# Sheet1.net
KiCad netlist of a schematic drawn in Altium Designer
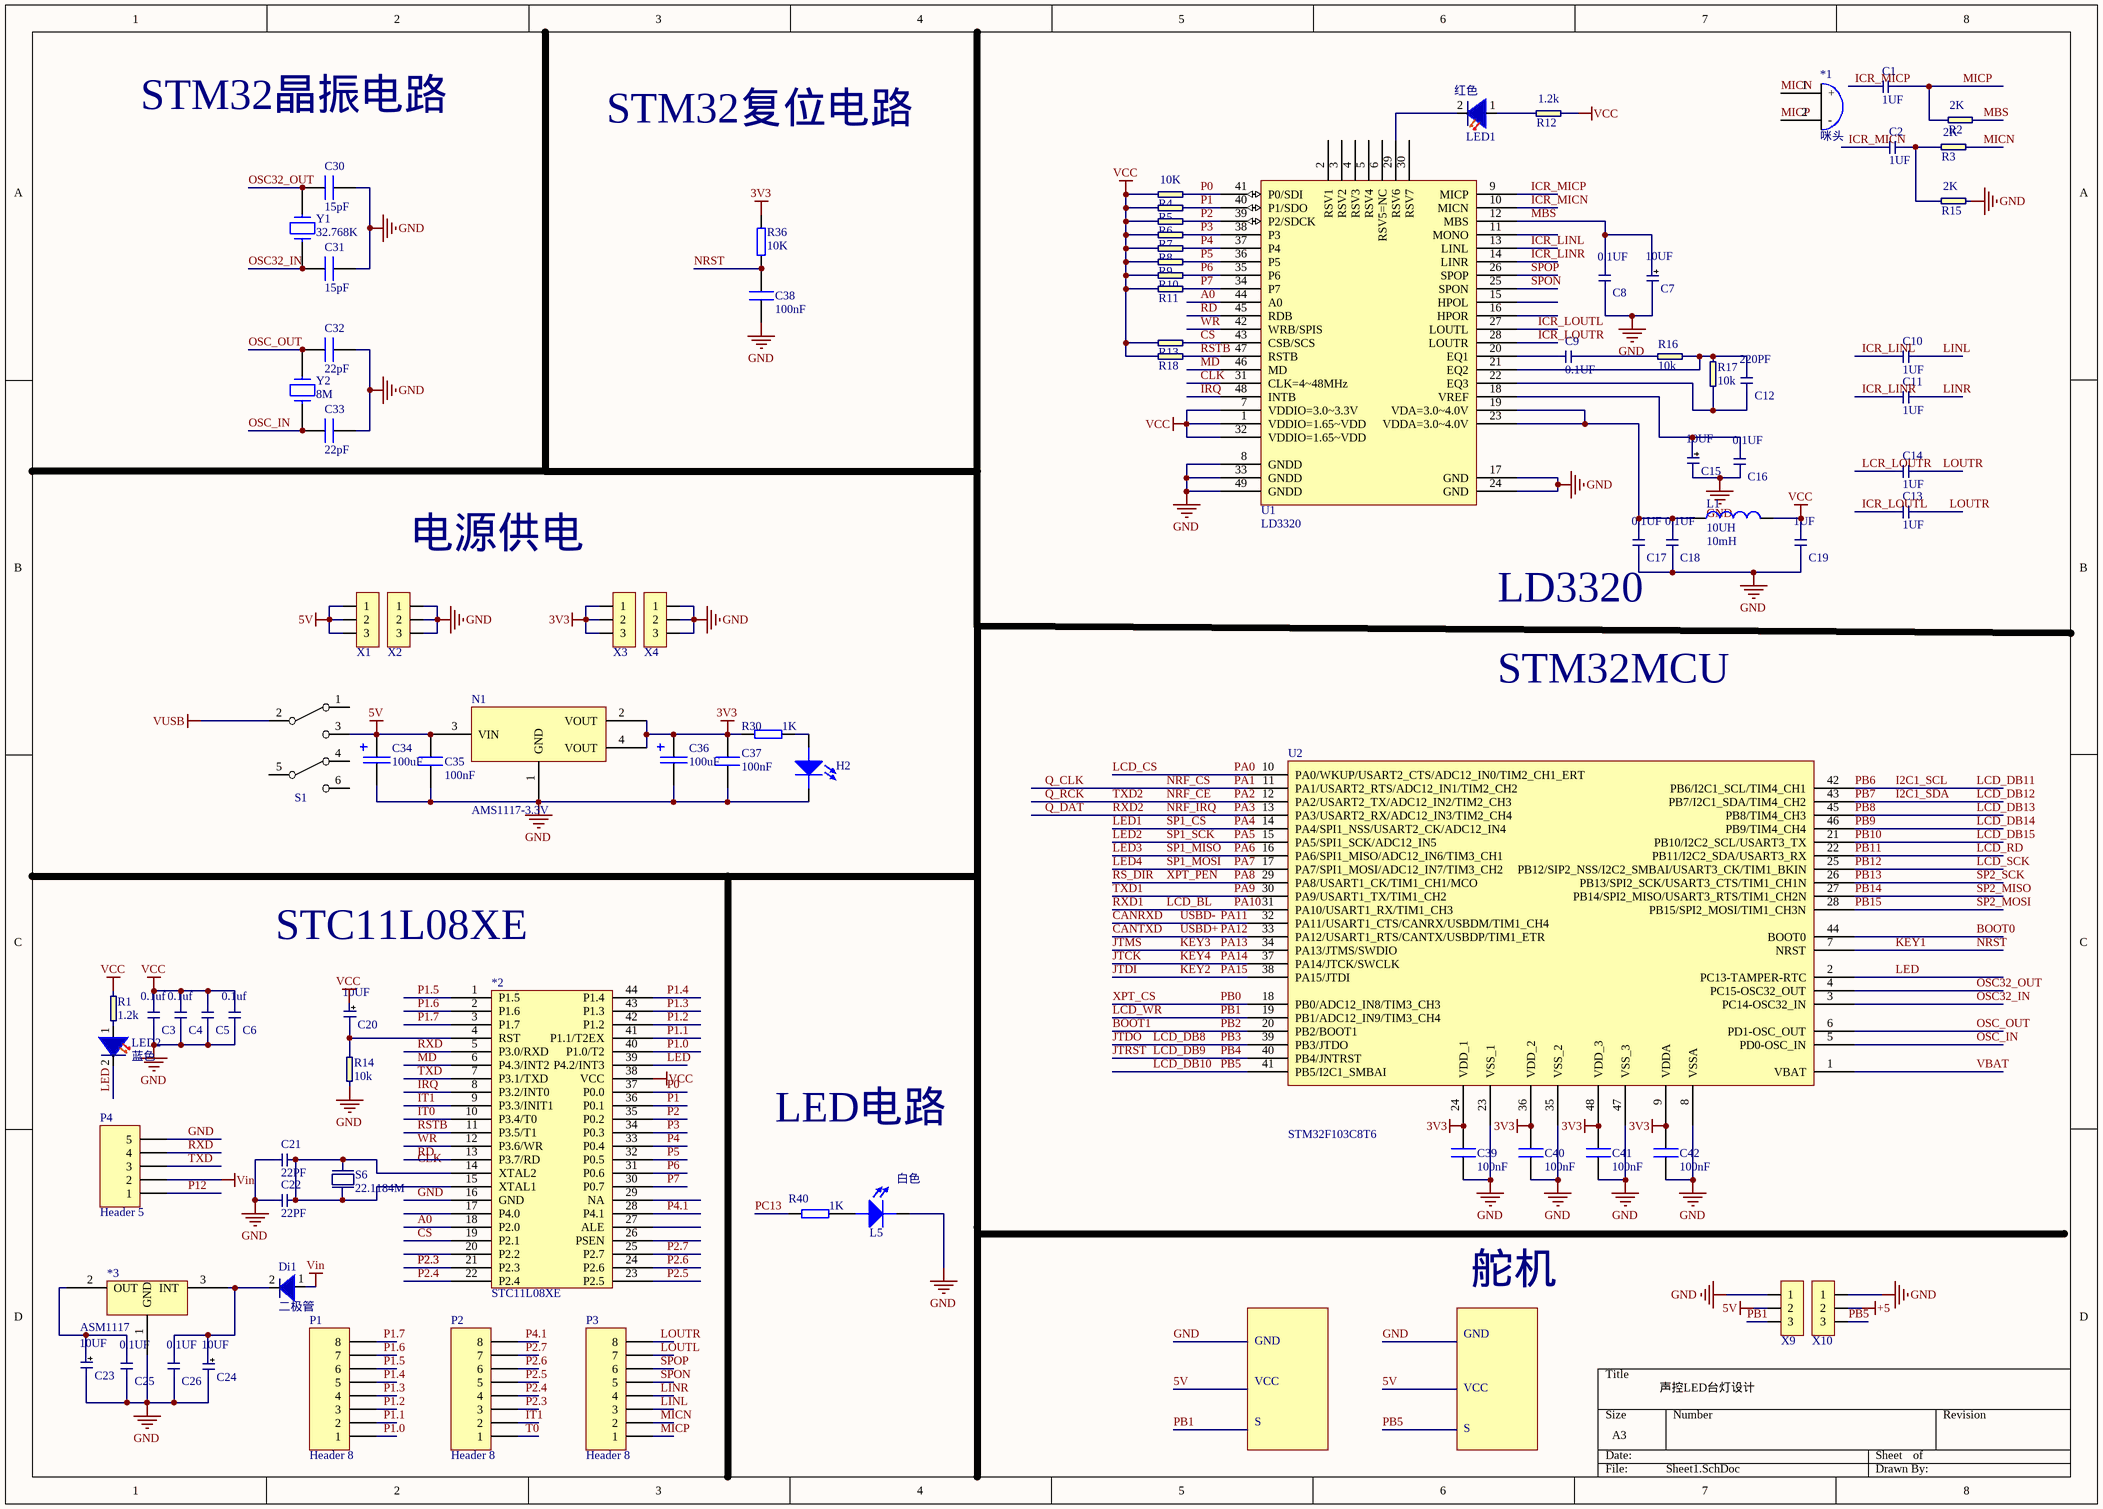
[diagram p0: Sheet1.SchDoc]

(export (version "E")
  (design (tool "Eeschema 10.0.6"))
  (components
    (comp (ref "*1") (value "咪头") (footprint "CAPPR5-5x5") (libsource (lib "LD3320原理图") (part "咪头")))
    (comp (ref "*2")
      (value "STC11L08XE")
      (footprint "LQFP44")
      (libsource (lib "LD3320原理图") (part "STC11L08XE"))
    )
    (comp (ref "*3") (value "ASM1117") (footprint "ASM1117") (libsource (lib "LD3320原理图") (part "ASM1117")))
    (comp (ref "C1") (value "1UF") (footprint "CT2mm") (libsource (lib "MYPCB") (part "瓷片电容")))
    (comp (ref "C2") (value "1UF") (footprint "CT2mm") (libsource (lib "MYPCB") (part "瓷片电容")))
    (comp (ref "C3") (value "0.1uf") (footprint "CT2mm") (libsource (lib "杨氏-元件库") (part "瓷片电容")))
    (comp (ref "C4") (value "0.1uf") (footprint "CT2mm") (libsource (lib "杨氏-元件库") (part "瓷片电容")))
    (comp (ref "C5") (value "0.1uf") (footprint "CT2mm") (libsource (lib "杨氏-元件库") (part "瓷片电容")))
    (comp (ref "C6") (value "0.1uf") (footprint "CT2mm") (libsource (lib "杨氏-元件库") (part "瓷片电容")))
    (comp (ref "C7") (value "10UF") (footprint "Rt2mm") (libsource (lib "MYPCB") (part "电解电容")))
    (comp (ref "C8") (value "0.1UF") (footprint "CT2mm") (libsource (lib "MYPCB") (part "瓷片电容")))
    (comp (ref "C9") (value "0.1UF") (footprint "CT2mm") (libsource (lib "MYPCB") (part "瓷片电容")))
    (comp (ref "C10") (value "1UF") (footprint "CT2mm") (libsource (lib "MYPCB") (part "瓷片电容")))
    (comp (ref "C11") (value "1UF") (footprint "CT2mm") (libsource (lib "MYPCB") (part "瓷片电容")))
    (comp (ref "C12") (value "220PF") (footprint "CT2mm") (libsource (lib "MYPCB") (part "瓷片电容")))
    (comp (ref "C13") (value "1UF") (footprint "CT2mm") (libsource (lib "MYPCB") (part "瓷片电容")))
    (comp (ref "C14") (value "1UF") (footprint "CT2mm") (libsource (lib "MYPCB") (part "瓷片电容")))
    (comp (ref "C15") (value "10UF") (footprint "Rt2mm") (libsource (lib "MYPCB") (part "电解电容")))
    (comp (ref "C16") (value "0.1UF") (footprint "CT2mm") (libsource (lib "MYPCB") (part "瓷片电容")))
    (comp (ref "C17") (value "0.1UF") (footprint "CT2mm") (libsource (lib "MYPCB") (part "瓷片电容")))
    (comp (ref "C18") (value "0.1UF") (footprint "CT2mm") (libsource (lib "MYPCB") (part "瓷片电容")))
    (comp (ref "C19") (value "1UF") (footprint "CT2mm") (libsource (lib "MYPCB") (part "瓷片电容")))
    (comp (ref "C20") (value "10UF") (footprint "Rt2mm") (libsource (lib "MYPCB") (part "电解电容")))
    (comp (ref "C21") (value "22PF") (footprint "CT2mm") (libsource (lib "MYPCB") (part "瓷片电容")))
    (comp (ref "C22") (value "22PF") (footprint "CT2mm") (libsource (lib "MYPCB") (part "瓷片电容")))
    (comp (ref "C23") (value "10UF") (footprint "Rt2mm") (libsource (lib "MYPCB") (part "电解电容")))
    (comp (ref "C24") (value "10UF") (footprint "Rt2mm") (libsource (lib "MYPCB") (part "电解电容")))
    (comp (ref "C25") (value "0.1UF") (footprint "CT2mm") (libsource (lib "MYPCB") (part "瓷片电容")))
    (comp (ref "C26") (value "0.1UF") (footprint "CT2mm") (libsource (lib "MYPCB") (part "瓷片电容")))
    (comp (ref "C30")
      (value "15pF")
      (footprint "C0805")
      (description "Capacitor")
      (libsource (lib "Liuzhx") (part "普通贴片电容"))
    )
    (comp (ref "C31")
      (value "15pF")
      (footprint "C0805")
      (description "Capacitor")
      (libsource (lib "Liuzhx") (part "普通贴片电容"))
    )
    (comp (ref "C32")
      (value "22pF")
      (footprint "C0805")
      (description "Capacitor")
      (libsource (lib "Liuzhx") (part "普通贴片电容"))
    )
    (comp (ref "C33")
      (value "22pF")
      (footprint "C0805")
      (description "Capacitor")
      (libsource (lib "Liuzhx") (part "普通贴片电容"))
    )
    (comp (ref "C34") (value "100uF") (footprint "CAP5*5_4") (libsource (lib "Liuzhx") (part "极性电容器")))
    (comp (ref "C35")
      (value "100nF")
      (footprint "C0805")
      (description "Capacitor")
      (libsource (lib "Liuzhx") (part "普通贴片电容"))
    )
    (comp (ref "C36") (value "100uF") (footprint "CAP5*5_4") (libsource (lib "Liuzhx") (part "极性电容器")))
    (comp (ref "C37")
      (value "100nF")
      (footprint "C0805")
      (description "Capacitor")
      (libsource (lib "Liuzhx") (part "普通贴片电容"))
    )
    (comp (ref "C38")
      (value "100nF")
      (footprint "C0805")
      (description "Capacitor")
      (libsource (lib "Liuzhx") (part "普通贴片电容"))
    )
    (comp (ref "C39")
      (value "100nF")
      (footprint "C0805")
      (description "Capacitor")
      (libsource (lib "Liuzhx") (part "普通贴片电容"))
    )
    (comp (ref "C40")
      (value "100nF")
      (footprint "C0805")
      (description "Capacitor")
      (libsource (lib "Liuzhx") (part "普通贴片电容"))
    )
    (comp (ref "C41")
      (value "100nF")
      (footprint "C0805")
      (description "Capacitor")
      (libsource (lib "Liuzhx") (part "普通贴片电容"))
    )
    (comp (ref "C42")
      (value "100nF")
      (footprint "C0805")
      (description "Capacitor")
      (libsource (lib "Liuzhx") (part "普通贴片电容"))
    )
    (comp (ref "Di1") (value "二极管") (footprint "DT4mm") (libsource (lib "MYPCB") (part "二极管")))
    (comp (ref "H2") (value "发光二极管") (footprint "LED1206") (libsource (lib "Liuzhx") (part "发光二极管")))
    (comp (ref "L1")
      (value "10UH")
      (footprint "INDC1005AL")
      (description "Inductor")
      (fields (field (name "ALTIUM_VALUE") "10mH") (field (name "PUBLISHER") "Altium Limited"))
      (libsource (lib "Miscellaneous Devices") (part "Inductor"))
    )
    (comp (ref "L5") (value "发光二极管") (footprint "LED1206") (libsource (lib "Liuzhx") (part "发光二极管")))
    (comp (ref "LED1") (value "红色") (footprint "LEDT") (libsource (lib "MYPCB") (part "LED")))
    (comp (ref "LED2") (value "蓝色") (footprint "LEDT") (libsource (lib "MYPCB") (part "LED")))
    (comp (ref "N1")
      (value "AMS1117-3.3V")
      (footprint "SOT223")
      (libsource (lib "Liuzhx") (part "AMS1117-3.3V"))
    )
    (comp (ref "P1")
      (value "Header 8")
      (footprint "HD8")
      (description "Header, 8-Pin")
      (fields (field (name "PUBLISHER") "Altium Limited"))
      (libsource (lib "MYPCB") (part "Header 8"))
    )
    (comp (ref "P2")
      (value "Header 8")
      (footprint "HD8")
      (description "Header, 8-Pin")
      (fields (field (name "PUBLISHER") "Altium Limited"))
      (libsource (lib "MYPCB") (part "Header 8"))
    )
    (comp (ref "P3")
      (value "Header 8")
      (footprint "HD8")
      (description "Header, 8-Pin")
      (fields (field (name "PUBLISHER") "Altium Limited"))
      (libsource (lib "MYPCB") (part "Header 8"))
    )
    (comp (ref "P4")
      (value "Header 5")
      (footprint "HD5")
      (description "Header, 5-Pin")
      (fields (field (name "PUBLISHER") "Altium Limited"))
      (libsource (lib "MYPCB") (part "Header 5"))
    )
    (comp (ref "R1") (value "1.2k") (footprint "Rt2mm") (libsource (lib "") (part "RES_2")))
    (comp (ref "R2") (value "2K") (footprint "Rt2mm") (libsource (lib "") (part "RES_1")))
    (comp (ref "R3") (value "2K") (footprint "Rt2mm") (libsource (lib "") (part "RES_1")))
    (comp (ref "R4") (value "10K") (footprint "Rt2mm") (libsource (lib "") (part "RES_1")))
    (comp (ref "R5") (value "RES") (footprint "Rt2mm") (libsource (lib "") (part "RES_1")))
    (comp (ref "R6") (value "RES") (footprint "Rt2mm") (libsource (lib "") (part "RES_1")))
    (comp (ref "R7") (value "RES") (footprint "Rt2mm") (libsource (lib "") (part "RES_1")))
    (comp (ref "R8") (value "RES") (footprint "Rt2mm") (libsource (lib "") (part "RES_1")))
    (comp (ref "R9") (value "RES") (footprint "Rt2mm") (libsource (lib "") (part "RES_1")))
    (comp (ref "R10") (value "RES") (footprint "Rt2mm") (libsource (lib "") (part "RES_1")))
    (comp (ref "R11") (value "RES") (footprint "Rt2mm") (libsource (lib "") (part "RES_1")))
    (comp (ref "R12") (value "1.2k") (footprint "Rt2mm") (libsource (lib "") (part "RES_1")))
    (comp (ref "R13") (value "RES") (footprint "Rt2mm") (libsource (lib "") (part "RES_1")))
    (comp (ref "R14") (value "10k") (footprint "Rt2mm") (libsource (lib "") (part "RES_2")))
    (comp (ref "R15") (value "2K") (footprint "Rt2mm") (libsource (lib "") (part "RES_1")))
    (comp (ref "R16") (value "10k") (footprint "Rt2mm") (libsource (lib "MYPCB") (part "RES")))
    (comp (ref "R17") (value "10k") (footprint "Rt2mm") (libsource (lib "") (part "RES_2")))
    (comp (ref "R18") (value "RES") (footprint "Rt2mm") (libsource (lib "") (part "RES_1")))
    (comp (ref "R30") (value "1K") (footprint "R0805") (libsource (lib "Liuzhx") (part "普通贴片电阻")))
    (comp (ref "R36") (value "10K") (footprint "R0805") (libsource (lib "Liuzhx") (part "普通贴片电阻")))
    (comp (ref "R40") (value "1K") (footprint "R0805") (libsource (lib "Liuzhx") (part "普通贴片电阻")))
    (comp (ref "S1") (value "SWITCH-6") (footprint "SW-AJ") (libsource (lib "Liuzhx") (part "SWITCH-6")))
    (comp (ref "S6") (value "22.1184M") (footprint "晶振") (libsource (lib "MYPCB") (part "Y1")))
    (comp (ref "U1")
      (value "LD3320")
      (footprint "QFN50P700X700X80-48N")
      (libsource (lib "LD3320原理图") (part "Component_1"))
    )
    (comp (ref "U2")
      (value "STM32F103C8T6")
      (footprint "LQFP48")
      (libsource (lib "STM32F103-V1.0") (part "STM32F103C8T6"))
    )
    (comp (ref "X1")
      (value "JX3")
      (footprint "SIP3")
      (description "Connector")
      (libsource (lib "") (part "JX3_1"))
    )
    (comp (ref "X2")
      (value "JX3")
      (footprint "SIP3")
      (description "Connector")
      (libsource (lib "Liuzhx") (part "JX3"))
    )
    (comp (ref "X3")
      (value "JX3")
      (footprint "SIP3")
      (description "Connector")
      (libsource (lib "") (part "JX3_1"))
    )
    (comp (ref "X4")
      (value "JX3")
      (footprint "SIP3")
      (description "Connector")
      (libsource (lib "Liuzhx") (part "JX3"))
    )
    (comp (ref "X9")
      (value "JX3")
      (footprint "SIP3")
      (description "Connector")
      (libsource (lib "") (part "JX3_1"))
    )
    (comp (ref "X10")
      (value "JX3")
      (footprint "SIP3")
      (description "Connector")
      (libsource (lib "Liuzhx") (part "JX3"))
    )
    (comp (ref "Y1")
      (value "32.768K")
      (footprint "FC135")
      (description "Crystal")
      (libsource (lib "Liuzhx") (part "CRYSTAL"))
    )
    (comp (ref "Y2")
      (value "8M")
      (footprint "JZ-AX")
      (description "Crystal")
      (libsource (lib "Liuzhx") (part "CRYSTAL"))
    )
  )
  (nets
    (net (code "1") (name "+5") (class "Default")
      (node (ref "X10") (pin "2") (pinfunction "2_2") (pintype "passive"))
    )
    (net (code "2") (name "/A0") (class "Default")
      (node (ref "*2") (pin "18") (pinfunction "P2.0_18") (pintype "passive"))
      (node (ref "U1") (pin "44") (pinfunction "A0_44") (pintype "passive"))
    )
    (net (code "3") (name "/BOOT0") (class "Default")
      (node (ref "U2") (pin "44") (pinfunction "BOOT0_44") (pintype "passive"))
    )
    (net (code "4") (name "/BOOT1") (class "Default")
      (node (ref "U2") (pin "20") (pinfunction "PB2/BOOT1_20") (pintype "passive"))
    )
    (net (code "5") (name "/CANRXD") (class "Default")
      (node (ref "U2") (pin "32") (pinfunction "PA11/USART1_CTS/CANRX/USBDM/TIM1_CH4_32") (pintype "passive"))
    )
    (net (code "6") (name "/CANTXD") (class "Default")
      (node (ref "U2") (pin "33") (pinfunction "PA12/USART1_RTS/CANTX/USBDP/TIM1_ETR_33") (pintype "passive"))
    )
    (net (code "7") (name "/CLK") (class "Default")
      (node (ref "U1") (pin "31") (pinfunction "CLK=4~48MHz_31") (pintype "passive"))
    )
    (net (code "8") (name "/CS") (class "Default")
      (node (ref "*2") (pin "19") (pinfunction "P2.1_19") (pintype "passive"))
      (node (ref "R13") (pin "2") (pinfunction "2_2") (pintype "passive"))
      (node (ref "U1") (pin "43") (pinfunction "CSB/SCS_43") (pintype "passive"))
    )
    (net (code "9") (name "/I2C1_SCL") (class "Default")
      (node (ref "U2") (pin "42") (pinfunction "PB6/I2C1_SCL/TIM4_CH1_42") (pintype "passive"))
    )
    (net (code "10") (name "/I2C1_SDA") (class "Default")
      (node (ref "U2") (pin "43") (pinfunction "PB7/I2C1_SDA/TIM4_CH2_43") (pintype "passive"))
    )
    (net (code "11") (name "/ICR_LINL") (class "Default")
      (node (ref "C10") (pin "2") (pinfunction "2_2") (pintype "passive"))
      (node (ref "U1") (pin "13") (pinfunction "LINL_13") (pintype "passive"))
    )
    (net (code "12") (name "/ICR_LINR") (class "Default")
      (node (ref "C11") (pin "2") (pinfunction "2_2") (pintype "passive"))
      (node (ref "U1") (pin "14") (pinfunction "LINR_14") (pintype "passive"))
    )
    (net (code "13") (name "/ICR_LOUTL") (class "Default")
      (node (ref "C13") (pin "2") (pinfunction "2_2") (pintype "passive"))
      (node (ref "U1") (pin "27") (pinfunction "LOUTL_27") (pintype "passive"))
    )
    (net (code "14") (name "/ICR_LOUTR") (class "Default")
      (node (ref "U1") (pin "28") (pinfunction "LOUTR_28") (pintype "passive"))
    )
    (net (code "15") (name "/ICR_MICN") (class "Default")
      (node (ref "C2") (pin "2") (pinfunction "2_2") (pintype "passive"))
      (node (ref "U1") (pin "10") (pinfunction "MICN_10") (pintype "passive"))
    )
    (net (code "16") (name "/ICR_MICP") (class "Default")
      (node (ref "C1") (pin "2") (pinfunction "2_2") (pintype "passive"))
      (node (ref "U1") (pin "9") (pinfunction "MICP_9") (pintype "passive"))
    )
    (net (code "17") (name "/IRQ") (class "Default")
      (node (ref "*2") (pin "8") (pinfunction "P3.2/INT0_8") (pintype "passive"))
      (node (ref "U1") (pin "48") (pinfunction "INTB_48") (pintype "passive"))
    )
    (net (code "18") (name "/IT0") (class "Default")
      (node (ref "*2") (pin "10") (pinfunction "P3.4/T0_10") (pintype "passive"))
    )
    (net (code "19") (name "/IT1") (class "Default")
      (node (ref "*2") (pin "9") (pinfunction "P3.3/INIT1_9") (pintype "passive"))
      (node (ref "P2") (pin "2") (pinfunction "2_2") (pintype "passive"))
    )
    (net (code "20") (name "/JTCK") (class "Default")
      (node (ref "U2") (pin "37") (pinfunction "PA14/JTCK/SWCLK_37") (pintype "passive"))
    )
    (net (code "21") (name "/JTDI") (class "Default")
      (node (ref "U2") (pin "38") (pinfunction "PA15/JTDI_38") (pintype "passive"))
    )
    (net (code "22") (name "/JTDO") (class "Default")
      (node (ref "U2") (pin "39") (pinfunction "PB3/JTDO_39") (pintype "passive"))
    )
    (net (code "23") (name "/JTMS") (class "Default")
      (node (ref "U2") (pin "34") (pinfunction "PA13/JTMS/SWDIO_34") (pintype "passive"))
    )
    (net (code "24") (name "/JTRST") (class "Default")
      (node (ref "U2") (pin "40") (pinfunction "PB4/JNTRST_40") (pintype "passive"))
    )
    (net (code "25") (name "/KEY1") (class "Default")
      (node (ref "C38") (pin "2") (pinfunction "2_2") (pintype "passive"))
      (node (ref "R36") (pin "1") (pinfunction "1_1") (pintype "passive"))
      (node (ref "U2") (pin "7") (pinfunction "NRST_7") (pintype "passive"))
    )
    (net (code "26") (name "/LCD_BL") (class "Default")
      (node (ref "U2") (pin "31") (pinfunction "PA10/USART1_RX/TIM1_CH3_31") (pintype "passive"))
    )
    (net (code "27") (name "/LCD_CS") (class "Default")
      (node (ref "U2") (pin "10") (pinfunction "PA0/WKUP/USART2_CTS/ADC12_IN0/TIM2_CH1_ERT_10") (pintype "passive"))
    )
    (net (code "28") (name "/LCD_DB10") (class "Default")
      (node (ref "U2") (pin "41") (pinfunction "PB5/I2C1_SMBAI_41") (pintype "passive"))
      (node (ref "X10") (pin "3") (pinfunction "3_3") (pintype "passive"))
    )
    (net (code "29") (name "/LCD_DB13") (class "Default")
      (node (ref "U2") (pin "45") (pinfunction "PB8/TIM4_CH3_45") (pintype "passive"))
    )
    (net (code "30") (name "/LCD_DB14") (class "Default")
      (node (ref "U2") (pin "46") (pinfunction "PB9/TIM4_CH4_46") (pintype "passive"))
    )
    (net (code "31") (name "/LCD_DB15") (class "Default")
      (node (ref "U2") (pin "21") (pinfunction "PB10/I2C2_SCL/USART3_TX_21") (pintype "passive"))
    )
    (net (code "32") (name "/LCD_RD") (class "Default")
      (node (ref "U2") (pin "22") (pinfunction "PB11/I2C2_SDA/USART3_RX_22") (pintype "passive"))
    )
    (net (code "33") (name "/LCD_SCK") (class "Default")
      (node (ref "U2") (pin "25") (pinfunction "PB12/SIP2_NSS/I2C2_SMBAI/USART3_CK/TIM1_BKIN_25") (pintype "passive"))
    )
    (net (code "34") (name "/LCD_WR") (class "Default")
      (node (ref "U2") (pin "19") (pinfunction "PB1/ADC12_IN9/TIM3_CH4_19") (pintype "passive"))
      (node (ref "X9") (pin "3") (pinfunction "3_3") (pintype "passive"))
    )
    (net (code "35") (name "/LCR_LOUTR") (class "Default")
      (node (ref "C14") (pin "2") (pinfunction "2_2") (pintype "passive"))
    )
    (net (code "36") (name "/LED") (class "Default")
      (node (ref "*2") (pin "39") (pinfunction "P4.2/INT3_39") (pintype "passive"))
      (node (ref "LED2") (pin "2") (pinfunction "2_2") (pintype "passive"))
      (node (ref "U2") (pin "2") (pinfunction "PC13-TAMPER-RTC_2") (pintype "passive"))
    )
    (net (code "37") (name "/LED1") (class "Default")
      (node (ref "U2") (pin "14") (pinfunction "PA4/SPI1_NSS/USART2_CK/ADC12_IN4_14") (pintype "passive"))
    )
    (net (code "38") (name "/LED2") (class "Default")
      (node (ref "U2") (pin "15") (pinfunction "PA5/SPI1_SCK/ADC12_IN5_15") (pintype "passive"))
    )
    (net (code "39") (name "/LED3") (class "Default")
      (node (ref "U2") (pin "16") (pinfunction "PA6/SPI1_MISO/ADC12_IN6/TIM3_CH1_16") (pintype "passive"))
    )
    (net (code "40") (name "/LED4") (class "Default")
      (node (ref "U2") (pin "17") (pinfunction "PA7/SPI1_MOSI/ADC12_IN7/TIM3_CH2_17") (pintype "passive"))
    )
    (net (code "41") (name "/LINL") (class "Default")
      (node (ref "C10") (pin "1") (pinfunction "1_1") (pintype "passive"))
      (node (ref "P3") (pin "3") (pinfunction "3_3") (pintype "passive"))
    )
    (net (code "42") (name "/LINR") (class "Default")
      (node (ref "C11") (pin "1") (pinfunction "1_1") (pintype "passive"))
      (node (ref "P3") (pin "4") (pinfunction "4_4") (pintype "passive"))
    )
    (net (code "43") (name "/LOUTL") (class "Default")
      (node (ref "P3") (pin "7") (pinfunction "7_7") (pintype "passive"))
    )
    (net (code "44") (name "/LOUTR") (class "Default")
      (node (ref "C13") (pin "1") (pinfunction "1_1") (pintype "passive"))
      (node (ref "C14") (pin "1") (pinfunction "1_1") (pintype "passive"))
      (node (ref "P3") (pin "8") (pinfunction "8_8") (pintype "passive"))
    )
    (net (code "45") (name "/MBS") (class "Default")
      (node (ref "C7") (pin "1") (pinfunction "1_1") (pintype "passive"))
      (node (ref "C8") (pin "2") (pinfunction "2_2") (pintype "passive"))
      (node (ref "R2") (pin "2") (pinfunction "2_2") (pintype "passive"))
      (node (ref "U1") (pin "12") (pinfunction "MBS_12") (pintype "passive"))
    )
    (net (code "46") (name "/MD") (class "Default")
      (node (ref "*2") (pin "6") (pinfunction "P4.3/INT2_6") (pintype "passive"))
      (node (ref "U1") (pin "46") (pinfunction "MD_46") (pintype "passive"))
    )
    (net (code "47") (name "/MICN") (class "Default")
      (node (ref "*1") (pin "1") (pinfunction "+_1") (pintype "passive"))
      (node (ref "P3") (pin "2") (pinfunction "2_2") (pintype "passive"))
      (node (ref "R3") (pin "2") (pinfunction "2_2") (pintype "passive"))
    )
    (net (code "48") (name "/MICP") (class "Default")
      (node (ref "*1") (pin "2") (pinfunction "-_2") (pintype "passive"))
      (node (ref "C1") (pin "1") (pinfunction "1_1") (pintype "passive"))
      (node (ref "P3") (pin "1") (pinfunction "1_1") (pintype "passive"))
      (node (ref "R2") (pin "1") (pinfunction "1_1") (pintype "passive"))
    )
    (net (code "49") (name "/NRF_CE") (class "Default")
      (node (ref "U2") (pin "12") (pinfunction "PA2/USART2_TX/ADC12_IN2/TIM2_CH3_12") (pintype "passive"))
    )
    (net (code "50") (name "/NRF_CS") (class "Default")
      (node (ref "U2") (pin "11") (pinfunction "PA1/USART2_RTS/ADC12_IN1/TIM2_CH2_11") (pintype "passive"))
    )
    (net (code "51") (name "/NRF_IRQ") (class "Default")
      (node (ref "U2") (pin "13") (pinfunction "PA3/USART2_RX/ADC12_IN3/TIM2_CH4_13") (pintype "passive"))
    )
    (net (code "52") (name "/OSC32_IN") (class "Default")
      (node (ref "C31") (pin "1") (pinfunction "1_1") (pintype "passive"))
      (node (ref "U2") (pin "3") (pinfunction "PC14-OSC32_IN_3") (pintype "passive"))
      (node (ref "Y1") (pin "1") (pinfunction "1_1") (pintype "passive"))
    )
    (net (code "53") (name "/OSC32_OUT") (class "Default")
      (node (ref "C30") (pin "1") (pinfunction "1_1") (pintype "passive"))
      (node (ref "U2") (pin "4") (pinfunction "PC15-OSC32_OUT_4") (pintype "passive"))
      (node (ref "Y1") (pin "2") (pinfunction "2_2") (pintype "passive"))
    )
    (net (code "54") (name "/OSC_IN") (class "Default")
      (node (ref "C33") (pin "1") (pinfunction "1_1") (pintype "passive"))
      (node (ref "U2") (pin "5") (pinfunction "PD0-OSC_IN_5") (pintype "passive"))
      (node (ref "Y2") (pin "1") (pinfunction "1_1") (pintype "passive"))
    )
    (net (code "55") (name "/OSC_OUT") (class "Default")
      (node (ref "C32") (pin "1") (pinfunction "1_1") (pintype "passive"))
      (node (ref "U2") (pin "6") (pinfunction "PD1-OSC_OUT_6") (pintype "passive"))
      (node (ref "Y2") (pin "2") (pinfunction "2_2") (pintype "passive"))
    )
    (net (code "56") (name "/P0") (class "Default")
      (node (ref "*2") (pin "37") (pinfunction "P0.0_37") (pintype "passive"))
      (node (ref "R4") (pin "2") (pinfunction "2_2") (pintype "passive"))
      (node (ref "U1") (pin "41") (pinfunction "P0/SDI_41") (pintype "bidirectional"))
    )
    (net (code "57") (name "/P1") (class "Default")
      (node (ref "*2") (pin "36") (pinfunction "P0.1_36") (pintype "passive"))
      (node (ref "R5") (pin "2") (pinfunction "2_2") (pintype "passive"))
      (node (ref "U1") (pin "40") (pinfunction "P1/SDO_40") (pintype "bidirectional"))
    )
    (net (code "58") (name "/P1.0") (class "Default")
      (node (ref "*2") (pin "40") (pinfunction "P1.0/T2_40") (pintype "passive"))
      (node (ref "P1") (pin "1") (pinfunction "1_1") (pintype "passive"))
    )
    (net (code "59") (name "/P1.1") (class "Default")
      (node (ref "*2") (pin "41") (pinfunction "P1.1/T2EX_41") (pintype "passive"))
      (node (ref "P1") (pin "2") (pinfunction "2_2") (pintype "passive"))
    )
    (net (code "60") (name "/P1.2") (class "Default")
      (node (ref "*2") (pin "42") (pinfunction "P1.2_42") (pintype "passive"))
      (node (ref "P1") (pin "3") (pinfunction "3_3") (pintype "passive"))
    )
    (net (code "61") (name "/P1.3") (class "Default")
      (node (ref "*2") (pin "43") (pinfunction "P1.3_43") (pintype "passive"))
      (node (ref "P1") (pin "4") (pinfunction "4_4") (pintype "passive"))
    )
    (net (code "62") (name "/P1.4") (class "Default")
      (node (ref "*2") (pin "44") (pinfunction "P1.4_44") (pintype "passive"))
      (node (ref "P1") (pin "5") (pinfunction "5_5") (pintype "passive"))
    )
    (net (code "63") (name "/P1.5") (class "Default")
      (node (ref "*2") (pin "1") (pinfunction "P1.5_1") (pintype "passive"))
      (node (ref "P1") (pin "6") (pinfunction "6_6") (pintype "passive"))
    )
    (net (code "64") (name "/P1.6") (class "Default")
      (node (ref "*2") (pin "2") (pinfunction "P1.6_2") (pintype "passive"))
      (node (ref "P1") (pin "7") (pinfunction "7_7") (pintype "passive"))
    )
    (net (code "65") (name "/P1.7") (class "Default")
      (node (ref "*2") (pin "3") (pinfunction "P1.7_3") (pintype "passive"))
      (node (ref "P1") (pin "8") (pinfunction "8_8") (pintype "passive"))
    )
    (net (code "66") (name "/P2") (class "Default")
      (node (ref "*2") (pin "35") (pinfunction "P0.2_35") (pintype "passive"))
      (node (ref "R6") (pin "2") (pinfunction "2_2") (pintype "passive"))
      (node (ref "U1") (pin "39") (pinfunction "P2/SDCK_39") (pintype "bidirectional"))
    )
    (net (code "67") (name "/P2.3") (class "Default")
      (node (ref "*2") (pin "21") (pinfunction "P2.3_21") (pintype "passive"))
      (node (ref "P2") (pin "3") (pinfunction "3_3") (pintype "passive"))
    )
    (net (code "68") (name "/P2.4") (class "Default")
      (node (ref "*2") (pin "22") (pinfunction "P2.4_22") (pintype "passive"))
      (node (ref "P2") (pin "4") (pinfunction "4_4") (pintype "passive"))
    )
    (net (code "69") (name "/P2.5") (class "Default")
      (node (ref "*2") (pin "23") (pinfunction "P2.5_23") (pintype "passive"))
      (node (ref "P2") (pin "5") (pinfunction "5_5") (pintype "passive"))
    )
    (net (code "70") (name "/P2.6") (class "Default")
      (node (ref "*2") (pin "24") (pinfunction "P2.6_24") (pintype "passive"))
      (node (ref "P2") (pin "6") (pinfunction "6_6") (pintype "passive"))
    )
    (net (code "71") (name "/P2.7") (class "Default")
      (node (ref "*2") (pin "25") (pinfunction "P2.7_25") (pintype "passive"))
      (node (ref "P2") (pin "7") (pinfunction "7_7") (pintype "passive"))
    )
    (net (code "72") (name "/P3") (class "Default")
      (node (ref "*2") (pin "34") (pinfunction "P0.3_34") (pintype "passive"))
      (node (ref "R7") (pin "2") (pinfunction "2_2") (pintype "passive"))
      (node (ref "U1") (pin "38") (pinfunction "P3_38") (pintype "passive"))
    )
    (net (code "73") (name "/P4") (class "Default")
      (node (ref "*2") (pin "33") (pinfunction "P0.4_33") (pintype "passive"))
      (node (ref "R8") (pin "2") (pinfunction "2_2") (pintype "passive"))
      (node (ref "U1") (pin "37") (pinfunction "P4_37") (pintype "passive"))
    )
    (net (code "74") (name "/P4.1") (class "Default")
      (node (ref "*2") (pin "28") (pinfunction "P4.1_28") (pintype "passive"))
      (node (ref "P2") (pin "8") (pinfunction "8_8") (pintype "passive"))
    )
    (net (code "75") (name "/P5") (class "Default")
      (node (ref "*2") (pin "32") (pinfunction "P0.5_32") (pintype "passive"))
      (node (ref "R9") (pin "2") (pinfunction "2_2") (pintype "passive"))
      (node (ref "U1") (pin "36") (pinfunction "P5_36") (pintype "passive"))
    )
    (net (code "76") (name "/P6") (class "Default")
      (node (ref "*2") (pin "31") (pinfunction "P0.6_31") (pintype "passive"))
      (node (ref "R10") (pin "2") (pinfunction "2_2") (pintype "passive"))
      (node (ref "U1") (pin "35") (pinfunction "P6_35") (pintype "passive"))
    )
    (net (code "77") (name "/P7") (class "Default")
      (node (ref "*2") (pin "30") (pinfunction "P0.7_30") (pintype "passive"))
      (node (ref "R11") (pin "2") (pinfunction "2_2") (pintype "passive"))
      (node (ref "U1") (pin "34") (pinfunction "P7_34") (pintype "passive"))
    )
    (net (code "78") (name "/P12") (class "Default")
      (node (ref "P4") (pin "1") (pinfunction "1_1") (pintype "passive"))
    )
    (net (code "79") (name "/PA8") (class "Default")
      (node (ref "U2") (pin "29") (pinfunction "PA8/USART1_CK/TIM1_CH1/MCO_29") (pintype "passive"))
    )
    (net (code "80") (name "/PA9") (class "Default")
      (node (ref "U2") (pin "30") (pinfunction "PA9/USART1_TX/TIM1_CH2_30") (pintype "passive"))
    )
    (net (code "81") (name "/PB0") (class "Default")
      (node (ref "U2") (pin "18") (pinfunction "PB0/ADC12_IN8/TIM3_CH3_18") (pintype "passive"))
    )
    (net (code "82") (name "/PB13") (class "Default")
      (node (ref "U2") (pin "26") (pinfunction "PB13/SPI2_SCK/USART3_CTS/TIM1_CH1N_26") (pintype "passive"))
    )
    (net (code "83") (name "/PB14") (class "Default")
      (node (ref "U2") (pin "27") (pinfunction "PB14/SPI2_MISO/USART3_RTS/TIM1_CH2N_27") (pintype "passive"))
    )
    (net (code "84") (name "/PB15") (class "Default")
      (node (ref "U2") (pin "28") (pinfunction "PB15/SPI2_MOSI/TIM1_CH3N_28") (pintype "passive"))
    )
    (net (code "85") (name "/PC13") (class "Default")
      (node (ref "R40") (pin "1") (pinfunction "1_1") (pintype "passive"))
    )
    (net (code "86") (name "/RD") (class "Default")
      (node (ref "*2") (pin "13") (pinfunction "P3.7/RD_13") (pintype "passive"))
      (node (ref "U1") (pin "45") (pinfunction "RDB_45") (pintype "passive"))
    )
    (net (code "87") (name "/RSTB") (class "Default")
      (node (ref "*2") (pin "11") (pinfunction "P3.5/T1_11") (pintype "passive"))
      (node (ref "R18") (pin "2") (pinfunction "2_2") (pintype "passive"))
      (node (ref "U1") (pin "47") (pinfunction "RSTB_47") (pintype "passive"))
    )
    (net (code "88") (name "/RXD") (class "Default")
      (node (ref "*2") (pin "5") (pinfunction "P3.0/RXD_5") (pintype "passive"))
      (node (ref "P4") (pin "4") (pinfunction "4_4") (pintype "passive"))
    )
    (net (code "89") (name "/SPON") (class "Default")
      (node (ref "P3") (pin "5") (pinfunction "5_5") (pintype "passive"))
      (node (ref "U1") (pin "25") (pinfunction "SPON_25") (pintype "passive"))
    )
    (net (code "90") (name "/SPOP") (class "Default")
      (node (ref "P3") (pin "6") (pinfunction "6_6") (pintype "passive"))
      (node (ref "U1") (pin "26") (pinfunction "SPOP_26") (pintype "passive"))
    )
    (net (code "91") (name "/T0") (class "Default")
      (node (ref "P2") (pin "1") (pinfunction "1_1") (pintype "passive"))
    )
    (net (code "92") (name "/TXD") (class "Default")
      (node (ref "*2") (pin "7") (pinfunction "P3.1/TXD_7") (pintype "passive"))
      (node (ref "P4") (pin "3") (pinfunction "3_3") (pintype "passive"))
    )
    (net (code "93") (name "/VBAT") (class "Default")
      (node (ref "U2") (pin "1") (pinfunction "VBAT_1") (pintype "passive"))
    )
    (net (code "94") (name "/WR") (class "Default")
      (node (ref "*2") (pin "12") (pinfunction "P3.6/WR_12") (pintype "passive"))
      (node (ref "U1") (pin "42") (pinfunction "WRB/SPIS_42") (pintype "passive"))
    )
    (net (code "95") (name "3V3") (class "Default")
      (node (ref "C36") (pin "1") (pinfunction "1_1") (pintype "passive"))
      (node (ref "C37") (pin "1") (pinfunction "1_1") (pintype "passive"))
      (node (ref "C39") (pin "1") (pinfunction "1_1") (pintype "passive"))
      (node (ref "C40") (pin "1") (pinfunction "1_1") (pintype "passive"))
      (node (ref "C41") (pin "1") (pinfunction "1_1") (pintype "passive"))
      (node (ref "C42") (pin "1") (pinfunction "1_1") (pintype "passive"))
      (node (ref "N1") (pin "2") (pinfunction "VOUT_2") (pintype "passive"))
      (node (ref "N1") (pin "4") (pinfunction "VOUT_4") (pintype "passive"))
      (node (ref "R30") (pin "1") (pinfunction "1_1") (pintype "passive"))
      (node (ref "R36") (pin "2") (pinfunction "2_2") (pintype "passive"))
      (node (ref "U2") (pin "24") (pinfunction "VDD_1_24") (pintype "passive"))
      (node (ref "U2") (pin "36") (pinfunction "VDD_2_36") (pintype "passive"))
      (node (ref "U2") (pin "48") (pinfunction "VDD_3_48") (pintype "passive"))
      (node (ref "U2") (pin "9") (pinfunction "VDDA_9") (pintype "passive"))
      (node (ref "X3") (pin "1") (pinfunction "1_1") (pintype "passive"))
      (node (ref "X3") (pin "2") (pinfunction "2_2") (pintype "passive"))
      (node (ref "X3") (pin "3") (pinfunction "3_3") (pintype "passive"))
    )
    (net (code "96") (name "5V") (class "Default")
      (node (ref "C34") (pin "1") (pinfunction "1_1") (pintype "passive"))
      (node (ref "C35") (pin "1") (pinfunction "1_1") (pintype "passive"))
      (node (ref "N1") (pin "3") (pinfunction "VIN_3") (pintype "passive"))
      (node (ref "S1") (pin "3") (pintype "passive"))
      (node (ref "X1") (pin "1") (pinfunction "1_1") (pintype "passive"))
      (node (ref "X1") (pin "2") (pinfunction "2_2") (pintype "passive"))
      (node (ref "X1") (pin "3") (pinfunction "3_3") (pintype "passive"))
      (node (ref "X9") (pin "2") (pinfunction "2_2") (pintype "passive"))
    )
    (net (code "97") (name "GND") (class "Default")
      (node (ref "*2") (pin "16") (pinfunction "GND_16") (pintype "passive"))
      (node (ref "*3") (pin "1") (pinfunction "GND_1") (pintype "passive"))
      (node (ref "C15") (pin "2") (pinfunction "2_2") (pintype "passive"))
      (node (ref "C16") (pin "1") (pinfunction "1_1") (pintype "passive"))
      (node (ref "C17") (pin "1") (pinfunction "1_1") (pintype "passive"))
      (node (ref "C18") (pin "1") (pinfunction "1_1") (pintype "passive"))
      (node (ref "C19") (pin "1") (pinfunction "1_1") (pintype "passive"))
      (node (ref "C21") (pin "2") (pinfunction "2_2") (pintype "passive"))
      (node (ref "C22") (pin "2") (pinfunction "2_2") (pintype "passive"))
      (node (ref "C23") (pin "2") (pinfunction "2_2") (pintype "passive"))
      (node (ref "C24") (pin "2") (pinfunction "2_2") (pintype "passive"))
      (node (ref "C25") (pin "1") (pinfunction "1_1") (pintype "passive"))
      (node (ref "C26") (pin "1") (pinfunction "1_1") (pintype "passive"))
      (node (ref "C3") (pin "1") (pinfunction "1_1") (pintype "passive"))
      (node (ref "C30") (pin "2") (pinfunction "2_2") (pintype "passive"))
      (node (ref "C31") (pin "2") (pinfunction "2_2") (pintype "passive"))
      (node (ref "C32") (pin "2") (pinfunction "2_2") (pintype "passive"))
      (node (ref "C33") (pin "2") (pinfunction "2_2") (pintype "passive"))
      (node (ref "C34") (pin "2") (pinfunction "2_2") (pintype "passive"))
      (node (ref "C35") (pin "2") (pinfunction "2_2") (pintype "passive"))
      (node (ref "C36") (pin "2") (pinfunction "2_2") (pintype "passive"))
      (node (ref "C37") (pin "2") (pinfunction "2_2") (pintype "passive"))
      (node (ref "C38") (pin "1") (pinfunction "1_1") (pintype "passive"))
      (node (ref "C39") (pin "2") (pinfunction "2_2") (pintype "passive"))
      (node (ref "C4") (pin "1") (pinfunction "1_1") (pintype "passive"))
      (node (ref "C40") (pin "2") (pinfunction "2_2") (pintype "passive"))
      (node (ref "C41") (pin "2") (pinfunction "2_2") (pintype "passive"))
      (node (ref "C42") (pin "2") (pinfunction "2_2") (pintype "passive"))
      (node (ref "C5") (pin "1") (pinfunction "1_1") (pintype "passive"))
      (node (ref "C6") (pin "1") (pinfunction "1_1") (pintype "passive"))
      (node (ref "C7") (pin "2") (pinfunction "2_2") (pintype "passive"))
      (node (ref "C8") (pin "1") (pinfunction "1_1") (pintype "passive"))
      (node (ref "H2") (pin "2") (pinfunction "K_2") (pintype "passive"))
      (node (ref "L5") (pin "2") (pinfunction "K_2") (pintype "passive"))
      (node (ref "N1") (pin "1") (pinfunction "GND_1") (pintype "passive"))
      (node (ref "P4") (pin "5") (pinfunction "5_5") (pintype "passive"))
      (node (ref "R14") (pin "1") (pinfunction "1_1") (pintype "passive"))
      (node (ref "R15") (pin "2") (pinfunction "2_2") (pintype "passive"))
      (node (ref "U1") (pin "17") (pinfunction "GND_17") (pintype "passive"))
      (node (ref "U1") (pin "24") (pinfunction "GND_24") (pintype "passive"))
      (node (ref "U1") (pin "33") (pinfunction "GNDD_33") (pintype "passive"))
      (node (ref "U1") (pin "49") (pinfunction "GNDD_49") (pintype "passive"))
      (node (ref "U1") (pin "8") (pinfunction "GNDD_8") (pintype "passive"))
      (node (ref "U2") (pin "23") (pinfunction "VSS_1_23") (pintype "passive"))
      (node (ref "U2") (pin "35") (pinfunction "VSS_2_35") (pintype "passive"))
      (node (ref "U2") (pin "47") (pinfunction "VSS_3_47") (pintype "passive"))
      (node (ref "U2") (pin "8") (pinfunction "VSSA_8") (pintype "passive"))
      (node (ref "X10") (pin "1") (pinfunction "1_1") (pintype "passive"))
      (node (ref "X2") (pin "1") (pinfunction "1_1") (pintype "passive"))
      (node (ref "X2") (pin "2") (pinfunction "2_2") (pintype "passive"))
      (node (ref "X2") (pin "3") (pinfunction "3_3") (pintype "passive"))
      (node (ref "X4") (pin "1") (pinfunction "1_1") (pintype "passive"))
      (node (ref "X4") (pin "2") (pinfunction "2_2") (pintype "passive"))
      (node (ref "X4") (pin "3") (pinfunction "3_3") (pintype "passive"))
      (node (ref "X9") (pin "1") (pinfunction "1_1") (pintype "passive"))
    )
    (net (code "98") (name "Net-(*2-RST)") (class "Default")
      (node (ref "*2") (pin "4") (pinfunction "RST_4") (pintype "passive"))
      (node (ref "C20") (pin "2") (pinfunction "2_2") (pintype "passive"))
      (node (ref "R14") (pin "2") (pinfunction "2_2") (pintype "passive"))
    )
    (net (code "99") (name "Net-(*2-XTAL1)") (class "Default")
      (node (ref "*2") (pin "14") (pinfunction "XTAL2_14") (pintype "passive"))
      (node (ref "*2") (pin "15") (pinfunction "XTAL1_15") (pintype "passive"))
      (node (ref "C21") (pin "1") (pinfunction "1_1") (pintype "passive"))
      (node (ref "C22") (pin "1") (pinfunction "1_1") (pintype "passive"))
      (node (ref "S6") (pin "1") (pinfunction "1_1") (pintype "passive"))
      (node (ref "S6") (pin "2") (pinfunction "2_2") (pintype "passive"))
    )
    (net (code "100") (name "Net-(*3-INT)") (class "Default")
      (node (ref "*3") (pin "3") (pinfunction "INT_3") (pintype "passive"))
      (node (ref "C24") (pin "1") (pinfunction "1_1") (pintype "passive"))
      (node (ref "C26") (pin "2") (pinfunction "2_2") (pintype "passive"))
      (node (ref "Di1") (pin "2") (pinfunction "2_2") (pintype "passive"))
    )
    (net (code "101") (name "Net-(*3-OUT)") (class "Default")
      (node (ref "*3") (pin "2") (pinfunction "OUT_2") (pintype "passive"))
      (node (ref "C23") (pin "1") (pinfunction "1_1") (pintype "passive"))
      (node (ref "C25") (pin "2") (pinfunction "2_2") (pintype "passive"))
    )
    (net (code "102") (name "Net-(C2-Pad1)") (class "Default")
      (node (ref "C2") (pin "1") (pinfunction "1_1") (pintype "passive"))
      (node (ref "R15") (pin "1") (pinfunction "1_1") (pintype "passive"))
      (node (ref "R3") (pin "1") (pinfunction "1_1") (pintype "passive"))
    )
    (net (code "103") (name "Net-(C9-Pad1)") (class "Default")
      (node (ref "C9") (pin "1") (pinfunction "1_1") (pintype "passive"))
      (node (ref "R16") (pin "2") (pinfunction "2_2") (pintype "passive"))
    )
    (net (code "104") (name "Net-(H2-A)") (class "Default")
      (node (ref "H2") (pin "1") (pinfunction "A_1") (pintype "passive"))
      (node (ref "R30") (pin "2") (pinfunction "2_2") (pintype "passive"))
    )
    (net (code "105") (name "Net-(L5-A)") (class "Default")
      (node (ref "L5") (pin "1") (pinfunction "A_1") (pintype "passive"))
      (node (ref "R40") (pin "2") (pinfunction "2_2") (pintype "passive"))
    )
    (net (code "106") (name "Net-(LED1-Pad1)") (class "Default")
      (node (ref "LED1") (pin "1") (pinfunction "1_1") (pintype "passive"))
      (node (ref "R12") (pin "1") (pinfunction "1_1") (pintype "passive"))
    )
    (net (code "107") (name "Net-(LED2-Pad1)") (class "Default")
      (node (ref "LED2") (pin "1") (pinfunction "1_1") (pintype "passive"))
      (node (ref "R1") (pin "1") (pinfunction "1_1") (pintype "passive"))
    )
    (net (code "108") (name "Net-(U1-EQ1)") (class "Default")
      (node (ref "C9") (pin "2") (pinfunction "2_2") (pintype "passive"))
      (node (ref "U1") (pin "20") (pinfunction "EQ1_20") (pintype "passive"))
    )
    (net (code "109") (name "Net-(U1-EQ2)") (class "Default")
      (node (ref "C12") (pin "2") (pinfunction "2_2") (pintype "passive"))
      (node (ref "R16") (pin "1") (pinfunction "1_1") (pintype "passive"))
      (node (ref "R17") (pin "2") (pinfunction "2_2") (pintype "passive"))
      (node (ref "U1") (pin "21") (pinfunction "EQ2_21") (pintype "passive"))
    )
    (net (code "110") (name "Net-(U1-EQ3)") (class "Default")
      (node (ref "C12") (pin "1") (pinfunction "1_1") (pintype "passive"))
      (node (ref "R17") (pin "1") (pinfunction "1_1") (pintype "passive"))
      (node (ref "U1") (pin "22") (pinfunction "EQ3_22") (pintype "passive"))
    )
    (net (code "111") (name "Net-(U1-RSV6)") (class "Default")
      (node (ref "LED1") (pin "2") (pinfunction "2_2") (pintype "passive"))
      (node (ref "U1") (pin "29") (pinfunction "RSV6_29") (pintype "passive"))
    )
    (net (code "112") (name "Net-(U1-VDA=3.0~4.0V)") (class "Default")
      (node (ref "C17") (pin "2") (pinfunction "2_2") (pintype "passive"))
      (node (ref "C18") (pin "2") (pinfunction "2_2") (pintype "passive"))
      (node (ref "L1") (pin "1") (pinfunction "1_1") (pintype "passive"))
      (node (ref "U1") (pin "19") (pinfunction "VDA=3.0~4.0V_19") (pintype "passive"))
      (node (ref "U1") (pin "23") (pinfunction "VDDA=3.0~4.0V_23") (pintype "passive"))
    )
    (net (code "113") (name "Net-(U1-VREF)") (class "Default")
      (node (ref "C15") (pin "1") (pinfunction "1_1") (pintype "passive"))
      (node (ref "C16") (pin "2") (pinfunction "2_2") (pintype "passive"))
      (node (ref "U1") (pin "18") (pinfunction "VREF_18") (pintype "passive"))
    )
    (net (code "114") (name "VCC") (class "Default")
      (node (ref "*2") (pin "38") (pinfunction "VCC_38") (pintype "passive"))
      (node (ref "C19") (pin "2") (pinfunction "2_2") (pintype "passive"))
      (node (ref "C20") (pin "1") (pinfunction "1_1") (pintype "passive"))
      (node (ref "C3") (pin "2") (pinfunction "2_2") (pintype "passive"))
      (node (ref "C4") (pin "2") (pinfunction "2_2") (pintype "passive"))
      (node (ref "C5") (pin "2") (pinfunction "2_2") (pintype "passive"))
      (node (ref "C6") (pin "2") (pinfunction "2_2") (pintype "passive"))
      (node (ref "L1") (pin "2") (pinfunction "2_2") (pintype "passive"))
      (node (ref "R1") (pin "2") (pinfunction "2_2") (pintype "passive"))
      (node (ref "R10") (pin "1") (pinfunction "1_1") (pintype "passive"))
      (node (ref "R11") (pin "1") (pinfunction "1_1") (pintype "passive"))
      (node (ref "R12") (pin "2") (pinfunction "2_2") (pintype "passive"))
      (node (ref "R13") (pin "1") (pinfunction "1_1") (pintype "passive"))
      (node (ref "R18") (pin "1") (pinfunction "1_1") (pintype "passive"))
      (node (ref "R4") (pin "1") (pinfunction "1_1") (pintype "passive"))
      (node (ref "R5") (pin "1") (pinfunction "1_1") (pintype "passive"))
      (node (ref "R6") (pin "1") (pinfunction "1_1") (pintype "passive"))
      (node (ref "R7") (pin "1") (pinfunction "1_1") (pintype "passive"))
      (node (ref "R8") (pin "1") (pinfunction "1_1") (pintype "passive"))
      (node (ref "R9") (pin "1") (pinfunction "1_1") (pintype "passive"))
      (node (ref "U1") (pin "1") (pinfunction "VDDIO=1.65~VDD_1") (pintype "passive"))
      (node (ref "U1") (pin "32") (pinfunction "VDDIO=1.65~VDD_32") (pintype "passive"))
      (node (ref "U1") (pin "7") (pinfunction "VDDIO=3.0~3.3V_7") (pintype "passive"))
    )
    (net (code "115") (name "VUSB") (class "Default") (node (ref "S1") (pin "2") (pintype "passive")))
    (net (code "116") (name "Vin") (class "Default")
      (node (ref "Di1") (pin "1") (pinfunction "1_1") (pintype "passive"))
      (node (ref "P4") (pin "2") (pinfunction "2_2") (pintype "passive"))
    )
    (net (code "117") (name "unconnected-(*2-ALE-Pad27)") (class "Default")
      (node (ref "*2") (pin "27") (pinfunction "ALE_27") (pintype "passive"))
    )
    (net (code "118") (name "unconnected-(*2-NA-Pad29)") (class "Default")
      (node (ref "*2") (pin "29") (pinfunction "NA_29") (pintype "passive"))
    )
    (net (code "119") (name "unconnected-(*2-P2.2-Pad20)") (class "Default")
      (node (ref "*2") (pin "20") (pinfunction "P2.2_20") (pintype "passive"))
    )
    (net (code "120") (name "unconnected-(*2-P4.0-Pad17)") (class "Default")
      (node (ref "*2") (pin "17") (pinfunction "P4.0_17") (pintype "passive"))
    )
    (net (code "121") (name "unconnected-(*2-PSEN-Pad26)") (class "Default")
      (node (ref "*2") (pin "26") (pinfunction "PSEN_26") (pintype "passive"))
    )
    (net (code "122") (name "unconnected-(S1-Pad1)") (class "Default")
      (node (ref "S1") (pin "1") (pintype "passive"))
    )
    (net (code "123") (name "unconnected-(S1-Pad4)") (class "Default")
      (node (ref "S1") (pin "4") (pintype "passive"))
    )
    (net (code "124") (name "unconnected-(S1-Pad5)") (class "Default")
      (node (ref "S1") (pin "5") (pintype "passive"))
    )
    (net (code "125") (name "unconnected-(S1-Pad6)") (class "Default")
      (node (ref "S1") (pin "6") (pintype "passive"))
    )
    (net (code "126") (name "unconnected-(U1-HPOL-Pad15)") (class "Default")
      (node (ref "U1") (pin "15") (pinfunction "HPOL_15") (pintype "passive"))
    )
    (net (code "127") (name "unconnected-(U1-HPOR-Pad16)") (class "Default")
      (node (ref "U1") (pin "16") (pinfunction "HPOR_16") (pintype "passive"))
    )
    (net (code "128") (name "unconnected-(U1-MONO-Pad11)") (class "Default")
      (node (ref "U1") (pin "11") (pinfunction "MONO_11") (pintype "passive"))
    )
    (net (code "129") (name "unconnected-(U1-RSV1-Pad2)") (class "Default")
      (node (ref "U1") (pin "2") (pinfunction "RSV1_2") (pintype "passive"))
    )
    (net (code "130") (name "unconnected-(U1-RSV2-Pad3)") (class "Default")
      (node (ref "U1") (pin "3") (pinfunction "RSV2_3") (pintype "passive"))
    )
    (net (code "131") (name "unconnected-(U1-RSV3-Pad4)") (class "Default")
      (node (ref "U1") (pin "4") (pinfunction "RSV3_4") (pintype "passive"))
    )
    (net (code "132") (name "unconnected-(U1-RSV4-Pad5)") (class "Default")
      (node (ref "U1") (pin "5") (pinfunction "RSV4_5") (pintype "passive"))
    )
    (net (code "133") (name "unconnected-(U1-RSV5=NC-Pad6)") (class "Default")
      (node (ref "U1") (pin "6") (pinfunction "RSV5=NC_6") (pintype "passive"))
    )
    (net (code "134") (name "unconnected-(U1-RSV7-Pad30)") (class "Default")
      (node (ref "U1") (pin "30") (pinfunction "RSV7_30") (pintype "passive"))
    )
  )
)
